# SSR.net
KiCad netlist of a schematic drawn in Altium Designer
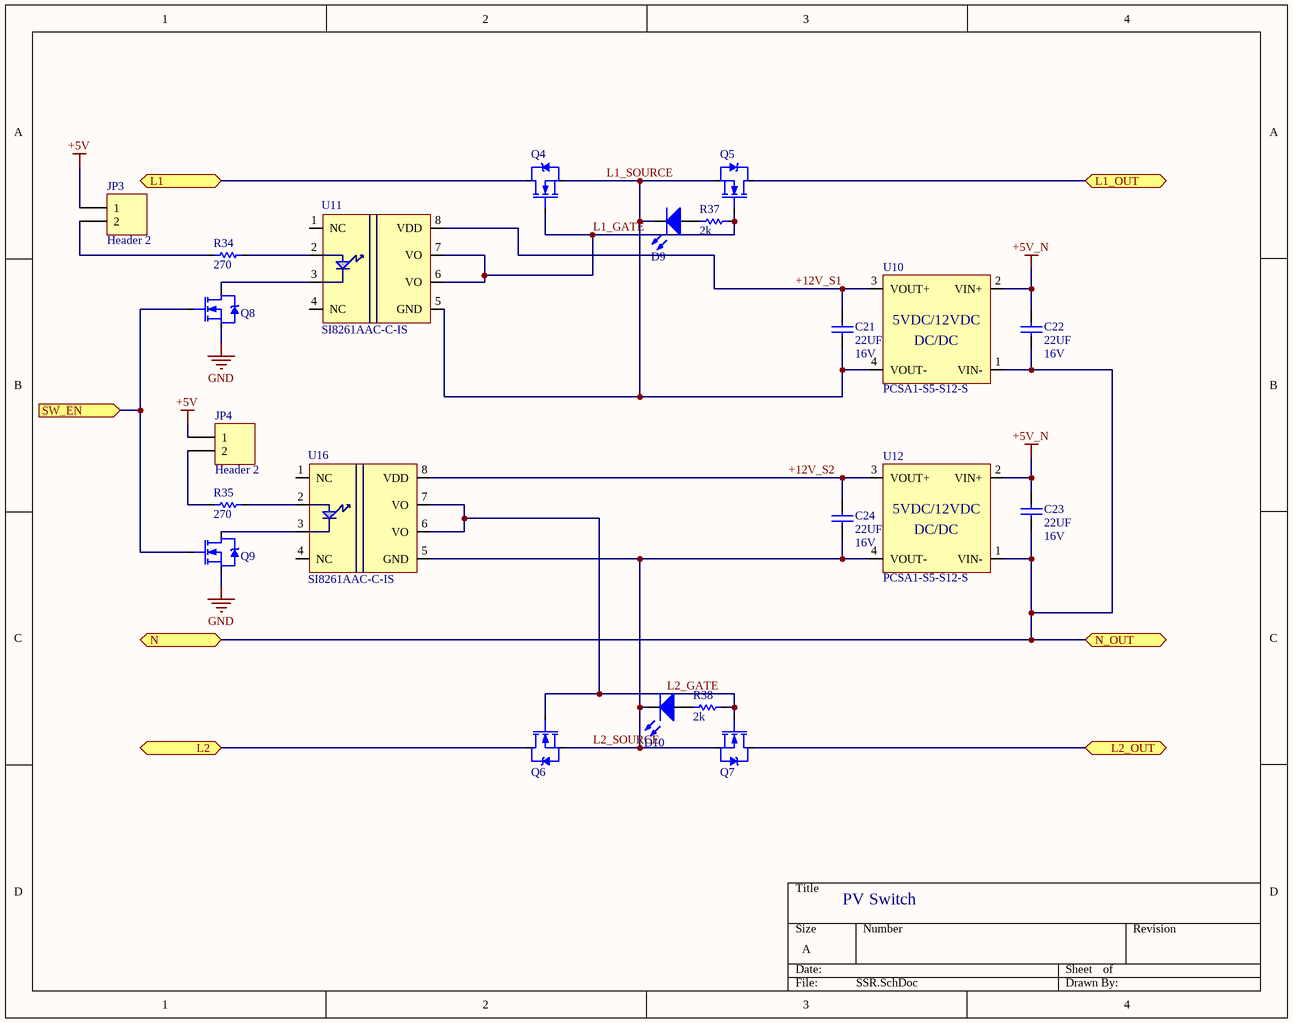
[diagram p0: SSR.SchDoc]

(export (version "E")
  (design (tool "Eeschema 10.0.6"))
  (components
    (comp (ref "C21")
      (value "GRM31CR61C226KE15K")
      (footprint "CAPC3216X16N")
      (description "CAP CER 22UF 16V X5R 1206")
      (fields
        (field (name "MANUFACTURER") "Murata Electronics North America")
        (field (name "CAPACITANCE") "22UF")
        (field (name "VOLTAGE - RATED") "16V")
      )
      (libsource (lib "IntelligentJunctionBox") (part "GRM31CR61C226KE15K"))
    )
    (comp (ref "C22")
      (value "GRM31CR61C226KE15K")
      (footprint "CAPC3216X16N")
      (description "CAP CER 22UF 16V X5R 1206")
      (fields
        (field (name "MANUFACTURER") "Murata Electronics North America")
        (field (name "CAPACITANCE") "22UF")
        (field (name "VOLTAGE - RATED") "16V")
      )
      (libsource (lib "IntelligentJunctionBox") (part "GRM31CR61C226KE15K"))
    )
    (comp (ref "C23")
      (value "GRM31CR61C226KE15K")
      (footprint "CAPC3216X16N")
      (description "CAP CER 22UF 16V X5R 1206")
      (fields
        (field (name "MANUFACTURER") "Murata Electronics North America")
        (field (name "CAPACITANCE") "22UF")
        (field (name "VOLTAGE - RATED") "16V")
      )
      (libsource (lib "IntelligentJunctionBox") (part "GRM31CR61C226KE15K"))
    )
    (comp (ref "C24")
      (value "GRM31CR61C226KE15K")
      (footprint "CAPC3216X16N")
      (description "CAP CER 22UF 16V X5R 1206")
      (fields
        (field (name "MANUFACTURER") "Murata Electronics North America")
        (field (name "CAPACITANCE") "22UF")
        (field (name "VOLTAGE - RATED") "16V")
      )
      (libsource (lib "IntelligentJunctionBox") (part "GRM31CR61C226KE15K"))
    )
    (comp (ref "D9")
      (value "LTST-C190KGKT")
      (footprint "0603 LED")
      (description "LED GREEN CLEAR 0603 SMD")
      (fields (field (name "MANUFACTURER") "Lite-On Inc."))
      (libsource (lib "IntelligentJunctionBox") (part "LTST-C190KGKT"))
    )
    (comp (ref "D10")
      (value "LTST-C190KGKT")
      (footprint "0603 LED")
      (description "LED GREEN CLEAR 0603 SMD")
      (fields (field (name "MANUFACTURER") "Lite-On Inc."))
      (libsource (lib "IntelligentJunctionBox") (part "LTST-C190KGKT"))
    )
    (comp (ref "JP3")
      (value "Header 2")
      (footprint "HDR1X2")
      (description "Header, 2-Pin")
      (fields
        (field (name "MANUFACTURER") "Sullins Connector Solutions")
        (field (name "MANUFACTURER PART NUMBER") "PBC36SAAN")
      )
      (libsource (lib "IntelligentJunctionBox") (part "Header 2"))
    )
    (comp (ref "JP4")
      (value "Header 2")
      (footprint "HDR1X2")
      (description "Header, 2-Pin")
      (fields
        (field (name "MANUFACTURER") "Sullins Connector Solutions")
        (field (name "MANUFACTURER PART NUMBER") "PBC36SAAN")
      )
      (libsource (lib "IntelligentJunctionBox") (part "Header 2"))
    )
    (comp (ref "Q4")
      (value "STB42N60M2-EP")
      (footprint "D2PAK")
      (description "MOSFET N-CH 600V 34A EP D2PAK")
      (fields (field (name "MANUFACTURER") "STMicroelectronics"))
      (libsource (lib "IntelligentJunctionBox") (part "STB42N60M2-EP"))
    )
    (comp (ref "Q5")
      (value "STB42N60M2-EP")
      (footprint "D2PAK")
      (description "MOSFET N-CH 600V 34A EP D2PAK")
      (fields (field (name "MANUFACTURER") "STMicroelectronics"))
      (libsource (lib "IntelligentJunctionBox") (part "STB42N60M2-EP"))
    )
    (comp (ref "Q6")
      (value "STB42N60M2-EP")
      (footprint "D2PAK")
      (description "MOSFET N-CH 600V 34A EP D2PAK")
      (fields (field (name "MANUFACTURER") "STMicroelectronics"))
      (libsource (lib "IntelligentJunctionBox") (part "STB42N60M2-EP"))
    )
    (comp (ref "Q7")
      (value "STB42N60M2-EP")
      (footprint "D2PAK")
      (description "MOSFET N-CH 600V 34A EP D2PAK")
      (fields (field (name "MANUFACTURER") "STMicroelectronics"))
      (libsource (lib "IntelligentJunctionBox") (part "STB42N60M2-EP"))
    )
    (comp (ref "Q8")
      (value "NTR5103NT1G")
      (footprint "SOT95P237X111-3N")
      (description "MOSFET N-CH 60V 0.26A SOT23")
      (fields (field (name "MANUFACTURER") "ON Semiconductor"))
      (libsource (lib "IntelligentJunctionBox") (part "NTR5103NT1G"))
    )
    (comp (ref "Q9")
      (value "NTR5103NT1G")
      (footprint "SOT95P237X111-3N")
      (description "MOSFET N-CH 60V 0.26A SOT23")
      (fields (field (name "MANUFACTURER") "ON Semiconductor"))
      (libsource (lib "IntelligentJunctionBox") (part "NTR5103NT1G"))
    )
    (comp (ref "R34")
      (value "RC0603JR-07270RL")
      (footprint "RESC1608X06N")
      (description "RES SMD 270 OHM 5% 1/10W 0603")
      (fields (field (name "MANUFACTURER") "Yageo") (field (name "RESISTANCE") "270"))
      (libsource (lib "IntelligentJunctionBox") (part "RC0603JR-07270RL"))
    )
    (comp (ref "R35")
      (value "RC0603JR-07270RL")
      (footprint "RESC1608X06N")
      (description "RES SMD 270 OHM 5% 1/10W 0603")
      (fields (field (name "MANUFACTURER") "Yageo") (field (name "RESISTANCE") "270"))
      (libsource (lib "IntelligentJunctionBox") (part "RC0603JR-07270RL"))
    )
    (comp (ref "R37")
      (value "RC0603FR-072KL")
      (footprint "RESC1608X06N")
      (description "RES SMD 2K OHM 1% 1/10W 0603")
      (fields (field (name "MANUFACTURER") "Yageo") (field (name "RESISTANCE") "2k"))
      (libsource (lib "IntelligentJunctionBox") (part "RC0603FR-072KL"))
    )
    (comp (ref "R38")
      (value "RC0603FR-072KL")
      (footprint "RESC1608X06N")
      (description "RES SMD 2K OHM 1% 1/10W 0603")
      (fields (field (name "MANUFACTURER") "Yageo") (field (name "RESISTANCE") "2k"))
      (libsource (lib "IntelligentJunctionBox") (part "RC0603FR-072KL"))
    )
    (comp (ref "U10")
      (value "PCSA1-S5-S12-S")
      (footprint "PCSA1-S5-S12-S")
      (description "DC/DC CONVERTER 5V-12V 1W")
      (fields (field (name "MANUFACTURER") "CUI Inc."))
      (libsource (lib "IntelligentJunctionBox") (part "PCSA1-S5-S12-S"))
    )
    (comp (ref "U11")
      (value "SI8261AAC-C-IS")
      (footprint "SOIC-8")
      (description "DGTL ISO 3.75KV GATE DRVR 8SOIC")
      (fields (field (name "MANUFACTURER") "Silicon Labs"))
      (libsource (lib "IntelligentJunctionBox") (part "SI8261AAC-C-IS"))
    )
    (comp (ref "U12")
      (value "PCSA1-S5-S12-S")
      (footprint "PCSA1-S5-S12-S")
      (description "DC/DC CONVERTER 5V-12V 1W")
      (fields (field (name "MANUFACTURER") "CUI Inc."))
      (libsource (lib "IntelligentJunctionBox") (part "PCSA1-S5-S12-S"))
    )
    (comp (ref "U16")
      (value "SI8261AAC-C-IS")
      (footprint "SOIC-8")
      (description "DGTL ISO 3.75KV GATE DRVR 8SOIC")
      (fields (field (name "MANUFACTURER") "Silicon Labs"))
      (libsource (lib "IntelligentJunctionBox") (part "SI8261AAC-C-IS"))
    )
  )
  (nets
    (net (code "1") (name "+5V") (class "Default")
      (node (ref "JP3") (pin "1") (pinfunction "1_1") (pintype "passive"))
      (node (ref "JP4") (pin "1") (pinfunction "1_1") (pintype "passive"))
    )
    (net (code "2") (name "+5V_N") (class "Default")
      (node (ref "C22") (pin "2") (pinfunction "2_2") (pintype "passive"))
      (node (ref "C23") (pin "2") (pinfunction "2_2") (pintype "passive"))
      (node (ref "U10") (pin "2") (pinfunction "VIN+_2") (pintype "passive"))
      (node (ref "U12") (pin "2") (pinfunction "VIN+_2") (pintype "passive"))
    )
    (net (code "3") (name "/+12V_S1") (class "Default")
      (node (ref "C21") (pin "2") (pinfunction "2_2") (pintype "passive"))
      (node (ref "U10") (pin "3") (pinfunction "VOUT+_3") (pintype "passive"))
      (node (ref "U11") (pin "8") (pinfunction "VDD_8") (pintype "passive"))
    )
    (net (code "4") (name "/+12V_S2") (class "Default")
      (node (ref "C24") (pin "2") (pinfunction "2_2") (pintype "passive"))
      (node (ref "U12") (pin "3") (pinfunction "VOUT+_3") (pintype "passive"))
      (node (ref "U16") (pin "8") (pinfunction "VDD_8") (pintype "passive"))
    )
    (net (code "5") (name "/L1") (class "Default")
      (node (ref "Q4") (pin "2") (pinfunction "D_2") (pintype "passive"))
    )
    (net (code "6") (name "/L1_GATE") (class "Default")
      (node (ref "Q4") (pin "1") (pinfunction "G_1") (pintype "passive"))
      (node (ref "Q5") (pin "1") (pinfunction "G_1") (pintype "passive"))
      (node (ref "R37") (pin "2") (pinfunction "2_2") (pintype "passive"))
      (node (ref "U11") (pin "6") (pinfunction "VO_6") (pintype "passive"))
      (node (ref "U11") (pin "7") (pinfunction "VO_7") (pintype "passive"))
    )
    (net (code "7") (name "/L1_OUT") (class "Default")
      (node (ref "Q5") (pin "2") (pinfunction "D_2") (pintype "passive"))
    )
    (net (code "8") (name "/L1_SOURCE") (class "Default")
      (node (ref "C21") (pin "1") (pinfunction "1_1") (pintype "passive"))
      (node (ref "D9") (pin "2") (pinfunction "K_2") (pintype "passive"))
      (node (ref "Q4") (pin "3") (pinfunction "S_3") (pintype "passive"))
      (node (ref "Q5") (pin "3") (pinfunction "S_3") (pintype "passive"))
      (node (ref "U10") (pin "4") (pinfunction "VOUT-_4") (pintype "passive"))
      (node (ref "U11") (pin "5") (pinfunction "GND_5") (pintype "passive"))
    )
    (net (code "9") (name "/L2") (class "Default")
      (node (ref "Q6") (pin "2") (pinfunction "D_2") (pintype "passive"))
    )
    (net (code "10") (name "/L2_GATE") (class "Default")
      (node (ref "Q6") (pin "1") (pinfunction "G_1") (pintype "passive"))
      (node (ref "Q7") (pin "1") (pinfunction "G_1") (pintype "passive"))
      (node (ref "R38") (pin "2") (pinfunction "2_2") (pintype "passive"))
      (node (ref "U16") (pin "6") (pinfunction "VO_6") (pintype "passive"))
      (node (ref "U16") (pin "7") (pinfunction "VO_7") (pintype "passive"))
    )
    (net (code "11") (name "/L2_OUT") (class "Default")
      (node (ref "Q7") (pin "2") (pinfunction "D_2") (pintype "passive"))
    )
    (net (code "12") (name "/L2_SOURCE") (class "Default")
      (node (ref "C24") (pin "1") (pinfunction "1_1") (pintype "passive"))
      (node (ref "D10") (pin "2") (pinfunction "K_2") (pintype "passive"))
      (node (ref "Q6") (pin "3") (pinfunction "S_3") (pintype "passive"))
      (node (ref "Q7") (pin "3") (pinfunction "S_3") (pintype "passive"))
      (node (ref "U12") (pin "4") (pinfunction "VOUT-_4") (pintype "passive"))
      (node (ref "U16") (pin "5") (pinfunction "GND_5") (pintype "passive"))
    )
    (net (code "13") (name "/N") (class "Default")
      (node (ref "C22") (pin "1") (pinfunction "1_1") (pintype "passive"))
      (node (ref "C23") (pin "1") (pinfunction "1_1") (pintype "passive"))
      (node (ref "U10") (pin "1") (pinfunction "VIN-_1") (pintype "passive"))
      (node (ref "U12") (pin "1") (pinfunction "VIN-_1") (pintype "passive"))
    )
    (net (code "14") (name "/SW_EN") (class "Default")
      (node (ref "Q8") (pin "1") (pinfunction "G_1") (pintype "passive"))
      (node (ref "Q9") (pin "1") (pinfunction "G_1") (pintype "passive"))
    )
    (net (code "15") (name "GND") (class "Default")
      (node (ref "Q8") (pin "2") (pinfunction "S_2") (pintype "passive"))
      (node (ref "Q9") (pin "2") (pinfunction "S_2") (pintype "passive"))
    )
    (net (code "16") (name "Net-(D9-A)") (class "Default")
      (node (ref "D9") (pin "1") (pinfunction "A_1") (pintype "passive"))
      (node (ref "R37") (pin "1") (pinfunction "1_1") (pintype "passive"))
    )
    (net (code "17") (name "Net-(D10-A)") (class "Default")
      (node (ref "D10") (pin "1") (pinfunction "A_1") (pintype "passive"))
      (node (ref "R38") (pin "1") (pinfunction "1_1") (pintype "passive"))
    )
    (net (code "18") (name "Net-(JP3-Pad2)") (class "Default")
      (node (ref "JP3") (pin "2") (pinfunction "2_2") (pintype "passive"))
      (node (ref "R34") (pin "1") (pinfunction "1_1") (pintype "passive"))
    )
    (net (code "19") (name "Net-(JP4-Pad2)") (class "Default")
      (node (ref "JP4") (pin "2") (pinfunction "2_2") (pintype "passive"))
      (node (ref "R35") (pin "1") (pinfunction "1_1") (pintype "passive"))
    )
    (net (code "20") (name "Net-(Q8-D)") (class "Default")
      (node (ref "Q8") (pin "3") (pinfunction "D_3") (pintype "passive"))
      (node (ref "U11") (pin "3") (pinfunction "K_3") (pintype "passive"))
    )
    (net (code "21") (name "Net-(Q9-D)") (class "Default")
      (node (ref "Q9") (pin "3") (pinfunction "D_3") (pintype "passive"))
      (node (ref "U16") (pin "3") (pinfunction "K_3") (pintype "passive"))
    )
    (net (code "22") (name "Net-(U11-A)") (class "Default")
      (node (ref "R34") (pin "2") (pinfunction "2_2") (pintype "passive"))
      (node (ref "U11") (pin "2") (pinfunction "A_2") (pintype "passive"))
    )
    (net (code "23") (name "Net-(U16-A)") (class "Default")
      (node (ref "R35") (pin "2") (pinfunction "2_2") (pintype "passive"))
      (node (ref "U16") (pin "2") (pinfunction "A_2") (pintype "passive"))
    )
    (net (code "24") (name "unconnected-(U11-NC-Pad1)") (class "Default")
      (node (ref "U11") (pin "1") (pinfunction "NC_1") (pintype "passive"))
    )
    (net (code "25") (name "unconnected-(U11-NC-Pad4)") (class "Default")
      (node (ref "U11") (pin "4") (pinfunction "NC_4") (pintype "passive"))
    )
    (net (code "26") (name "unconnected-(U16-NC-Pad1)") (class "Default")
      (node (ref "U16") (pin "1") (pinfunction "NC_1") (pintype "passive"))
    )
    (net (code "27") (name "unconnected-(U16-NC-Pad4)") (class "Default")
      (node (ref "U16") (pin "4") (pinfunction "NC_4") (pintype "passive"))
    )
  )
)
